# ton-bot.net
KiCad netlist of a schematic drawn in EAGLE
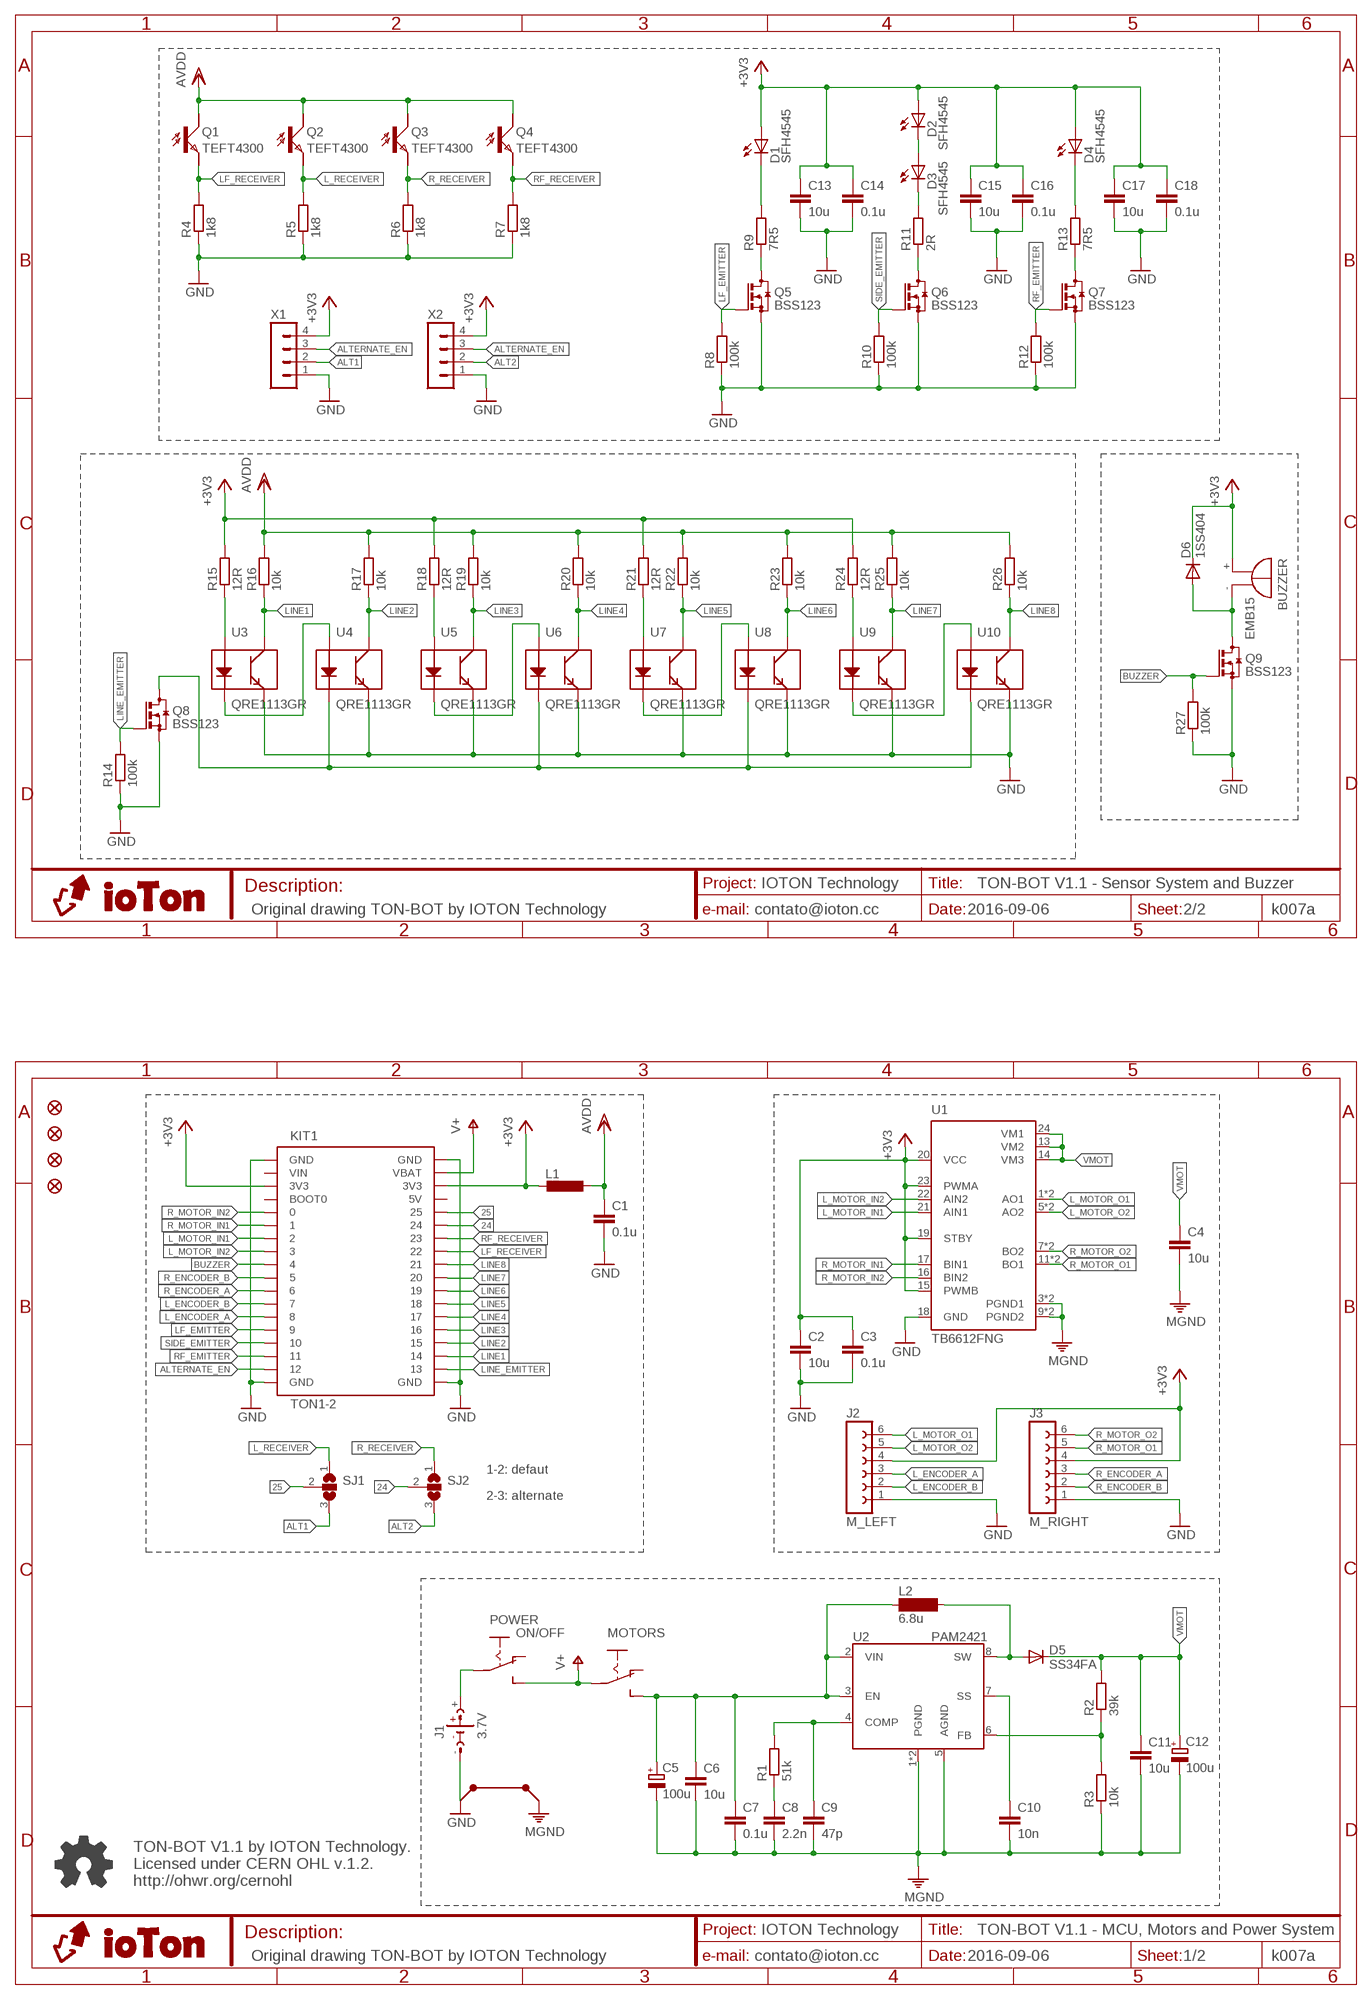
[diagram p0: schematic, sheet 1]

(export (version "E")
  (design (tool "Eeschema 10.0.6"))
  (components
    (comp (ref "BUZZER")
      (value "EMB15")
      (footprint "eagle-import:BMT1205XH7.5")
      (libsource (lib "eagle-import") (part "BMT1205XH7.5"))
    )
    (comp (ref "C1")
      (value "0.1u")
      (footprint "eagle-import:C0603")
      (libsource (lib "eagle-import") (part "C-EUC0603"))
    )
    (comp (ref "C2")
      (value "10u")
      (footprint "eagle-import:C0805")
      (libsource (lib "eagle-import") (part "C-EUC0805"))
    )
    (comp (ref "C3")
      (value "0.1u")
      (footprint "eagle-import:C0603")
      (libsource (lib "eagle-import") (part "C-EUC0603"))
    )
    (comp (ref "C4")
      (value "10u")
      (footprint "eagle-import:C0805")
      (libsource (lib "eagle-import") (part "C-EUC0805"))
    )
    (comp (ref "C5")
      (value "100u")
      (footprint "eagle-import:153CLV-0505")
      (libsource (lib "eagle-import") (part "CPOL-EU153CLV-0505"))
    )
    (comp (ref "C6")
      (value "10u")
      (footprint "eagle-import:C0805")
      (libsource (lib "eagle-import") (part "C-EUC0805"))
    )
    (comp (ref "C7")
      (value "0.1u")
      (footprint "eagle-import:C0603")
      (libsource (lib "eagle-import") (part "C-EUC0603"))
    )
    (comp (ref "C8")
      (value "2.2n")
      (footprint "eagle-import:C0603")
      (libsource (lib "eagle-import") (part "C-EUC0603"))
    )
    (comp (ref "C9")
      (value "47p")
      (footprint "eagle-import:C0603")
      (libsource (lib "eagle-import") (part "C-EUC0603"))
    )
    (comp (ref "C10")
      (value "10n")
      (footprint "eagle-import:C0603")
      (libsource (lib "eagle-import") (part "C-EUC0603"))
    )
    (comp (ref "C11")
      (value "10u")
      (footprint "eagle-import:C0805")
      (libsource (lib "eagle-import") (part "C-EUC0805"))
    )
    (comp (ref "C12")
      (value "100u")
      (footprint "eagle-import:153CLV-0505")
      (libsource (lib "eagle-import") (part "CPOL-EU153CLV-0505"))
    )
    (comp (ref "C13")
      (value "10u")
      (footprint "eagle-import:C0805")
      (libsource (lib "eagle-import") (part "C-EUC0805"))
    )
    (comp (ref "C14")
      (value "0.1u")
      (footprint "eagle-import:C0603")
      (libsource (lib "eagle-import") (part "C-EUC0603"))
    )
    (comp (ref "C15")
      (value "10u")
      (footprint "eagle-import:C0805")
      (libsource (lib "eagle-import") (part "C-EUC0805"))
    )
    (comp (ref "C16")
      (value "0.1u")
      (footprint "eagle-import:C0603")
      (libsource (lib "eagle-import") (part "C-EUC0603"))
    )
    (comp (ref "C17")
      (value "10u")
      (footprint "eagle-import:C0805")
      (libsource (lib "eagle-import") (part "C-EUC0805"))
    )
    (comp (ref "C18")
      (value "0.1u")
      (footprint "eagle-import:C0603")
      (libsource (lib "eagle-import") (part "C-EUC0603"))
    )
    (comp (ref "D1")
      (value "SFH4545")
      (footprint "eagle-import:SFH4545-AK")
      (libsource (lib "eagle-import") (part "SFH4545AK"))
    )
    (comp (ref "D2")
      (value "SFH4545")
      (footprint "eagle-import:SFH4545-KA")
      (libsource (lib "eagle-import") (part "SFH4545KA"))
    )
    (comp (ref "D3")
      (value "SFH4545")
      (footprint "eagle-import:SFH4545-KA")
      (libsource (lib "eagle-import") (part "SFH4545KA"))
    )
    (comp (ref "D4")
      (value "SFH4545")
      (footprint "eagle-import:SFH4545-KA")
      (libsource (lib "eagle-import") (part "SFH4545KA"))
    )
    (comp (ref "D5")
      (value "SS34FA")
      (footprint "eagle-import:DO214BA")
      (libsource (lib "eagle-import") (part "DIODE-DO214BA"))
    )
    (comp (ref "D6")
      (value "1SS404")
      (footprint "eagle-import:SOD323-R")
      (libsource (lib "eagle-import") (part "DIODE-SOD323-R"))
    )
    (comp (ref "J1")
      (value "3.7V")
      (footprint "eagle-import:BATTERY")
      (libsource (lib "eagle-import") (part "BATTERY"))
    )
    (comp (ref "J2")
      (value "M_LEFT")
      (footprint "eagle-import:CON6-1_2MM")
      (libsource (lib "eagle-import") (part "FE06-12MM"))
    )
    (comp (ref "J3")
      (value "M_RIGHT")
      (footprint "eagle-import:CON6-1_2MM")
      (libsource (lib "eagle-import") (part "FE06-12MM"))
    )
    (comp (ref "JP1")
      (value "FIDUCIAL1X2")
      (footprint "eagle-import:FIDUCIAL-1X2")
      (libsource (lib "eagle-import") (part "FIDUCIAL1X2"))
    )
    (comp (ref "JP2")
      (value "FIDUCIAL1X2")
      (footprint "eagle-import:FIDUCIAL-1X2")
      (libsource (lib "eagle-import") (part "FIDUCIAL1X2"))
    )
    (comp (ref "JP3")
      (value "FIDUCIAL1X2")
      (footprint "eagle-import:FIDUCIAL-1X2")
      (libsource (lib "eagle-import") (part "FIDUCIAL1X2"))
    )
    (comp (ref "JP4")
      (value "FIDUCIAL1X2")
      (footprint "eagle-import:FIDUCIAL-1X2")
      (libsource (lib "eagle-import") (part "FIDUCIAL1X2"))
    )
    (comp (ref "KIT1")
      (value "TON1-2")
      (footprint "eagle-import:TON1-2")
      (libsource (lib "eagle-import") (part "TON1-2"))
    )
    (comp (ref "L1")
      (value "L-EUL0603")
      (footprint "eagle-import:L0603")
      (libsource (lib "eagle-import") (part "L-EUL0603"))
    )
    (comp (ref "L2")
      (value "6.8u")
      (footprint "eagle-import:TYS6045")
      (libsource (lib "eagle-import") (part "TYS6045"))
    )
    (comp (ref "MOTORS")
      (value "SWITCHS")
      (footprint "eagle-import:SWITCH")
      (libsource (lib "eagle-import") (part "SWITCHS"))
    )
    (comp (ref "POWER")
      (value "ON/OFF")
      (footprint "eagle-import:SWITCH")
      (libsource (lib "eagle-import") (part "SWITCHS"))
    )
    (comp (ref "Q1")
      (value "TEFT4300")
      (footprint "eagle-import:TEFT4300-CE")
      (libsource (lib "eagle-import") (part "TEFT4300CE"))
    )
    (comp (ref "Q2")
      (value "TEFT4300")
      (footprint "eagle-import:TEFT4300-EC")
      (libsource (lib "eagle-import") (part "TEFT4300EC"))
    )
    (comp (ref "Q3")
      (value "TEFT4300")
      (footprint "eagle-import:TEFT4300-CE")
      (libsource (lib "eagle-import") (part "TEFT4300CE"))
    )
    (comp (ref "Q4")
      (value "TEFT4300")
      (footprint "eagle-import:TEFT4300-EC")
      (libsource (lib "eagle-import") (part "TEFT4300EC"))
    )
    (comp (ref "Q5")
      (value "BSS123")
      (footprint "eagle-import:SOT23")
      (libsource (lib "eagle-import") (part "BSS123"))
    )
    (comp (ref "Q6")
      (value "BSS123")
      (footprint "eagle-import:SOT23")
      (libsource (lib "eagle-import") (part "BSS123"))
    )
    (comp (ref "Q7")
      (value "BSS123")
      (footprint "eagle-import:SOT23")
      (libsource (lib "eagle-import") (part "BSS123"))
    )
    (comp (ref "Q8")
      (value "BSS123")
      (footprint "eagle-import:SOT23")
      (libsource (lib "eagle-import") (part "BSS123"))
    )
    (comp (ref "Q9")
      (value "BSS123")
      (footprint "eagle-import:SOT23")
      (libsource (lib "eagle-import") (part "BSS123"))
    )
    (comp (ref "R1")
      (value "51k")
      (footprint "eagle-import:R0603")
      (libsource (lib "eagle-import") (part "R-EU_R0603"))
    )
    (comp (ref "R2")
      (value "39k")
      (footprint "eagle-import:R0603")
      (libsource (lib "eagle-import") (part "R-EU_R0603"))
    )
    (comp (ref "R3")
      (value "10k")
      (footprint "eagle-import:R0603")
      (libsource (lib "eagle-import") (part "R-EU_R0603"))
    )
    (comp (ref "R4")
      (value "1k8")
      (footprint "eagle-import:R0603")
      (libsource (lib "eagle-import") (part "R-EU_R0603"))
    )
    (comp (ref "R5")
      (value "1k8")
      (footprint "eagle-import:R0603")
      (libsource (lib "eagle-import") (part "R-EU_R0603"))
    )
    (comp (ref "R6")
      (value "1k8")
      (footprint "eagle-import:R0603")
      (libsource (lib "eagle-import") (part "R-EU_R0603"))
    )
    (comp (ref "R7")
      (value "1k8")
      (footprint "eagle-import:R0603")
      (libsource (lib "eagle-import") (part "R-EU_R0603"))
    )
    (comp (ref "R8")
      (value "100k")
      (footprint "eagle-import:R0603")
      (libsource (lib "eagle-import") (part "R-EU_R0603"))
    )
    (comp (ref "R9")
      (value "7R5")
      (footprint "eagle-import:R0805")
      (libsource (lib "eagle-import") (part "R-EU_R0805"))
    )
    (comp (ref "R10")
      (value "100k")
      (footprint "eagle-import:R0603")
      (libsource (lib "eagle-import") (part "R-EU_R0603"))
    )
    (comp (ref "R11")
      (value "2R")
      (footprint "eagle-import:R0805")
      (libsource (lib "eagle-import") (part "R-EU_R0805"))
    )
    (comp (ref "R12")
      (value "100k")
      (footprint "eagle-import:R0603")
      (libsource (lib "eagle-import") (part "R-EU_R0603"))
    )
    (comp (ref "R13")
      (value "7R5")
      (footprint "eagle-import:R0805")
      (libsource (lib "eagle-import") (part "R-EU_R0805"))
    )
    (comp (ref "R14")
      (value "100k")
      (footprint "eagle-import:R0603")
      (libsource (lib "eagle-import") (part "R-EU_R0603"))
    )
    (comp (ref "R15")
      (value "12R")
      (footprint "eagle-import:R0603")
      (libsource (lib "eagle-import") (part "R-EU_R0603"))
    )
    (comp (ref "R16")
      (value "10k")
      (footprint "eagle-import:R0603")
      (libsource (lib "eagle-import") (part "R-EU_R0603"))
    )
    (comp (ref "R17")
      (value "10k")
      (footprint "eagle-import:R0603")
      (libsource (lib "eagle-import") (part "R-EU_R0603"))
    )
    (comp (ref "R18")
      (value "12R")
      (footprint "eagle-import:R0603")
      (libsource (lib "eagle-import") (part "R-EU_R0603"))
    )
    (comp (ref "R19")
      (value "10k")
      (footprint "eagle-import:R0603")
      (libsource (lib "eagle-import") (part "R-EU_R0603"))
    )
    (comp (ref "R20")
      (value "10k")
      (footprint "eagle-import:R0603")
      (libsource (lib "eagle-import") (part "R-EU_R0603"))
    )
    (comp (ref "R21")
      (value "12R")
      (footprint "eagle-import:R0603")
      (libsource (lib "eagle-import") (part "R-EU_R0603"))
    )
    (comp (ref "R22")
      (value "10k")
      (footprint "eagle-import:R0603")
      (libsource (lib "eagle-import") (part "R-EU_R0603"))
    )
    (comp (ref "R23")
      (value "10k")
      (footprint "eagle-import:R0603")
      (libsource (lib "eagle-import") (part "R-EU_R0603"))
    )
    (comp (ref "R24")
      (value "12R")
      (footprint "eagle-import:R0603")
      (libsource (lib "eagle-import") (part "R-EU_R0603"))
    )
    (comp (ref "R25")
      (value "10k")
      (footprint "eagle-import:R0603")
      (libsource (lib "eagle-import") (part "R-EU_R0603"))
    )
    (comp (ref "R26")
      (value "10k")
      (footprint "eagle-import:R0603")
      (libsource (lib "eagle-import") (part "R-EU_R0603"))
    )
    (comp (ref "R27")
      (value "100k")
      (footprint "eagle-import:R0603")
      (libsource (lib "eagle-import") (part "R-EU_R0603"))
    )
    (comp (ref "SJ1")
      (value "SJ2W")
      (footprint "eagle-import:SJ_2")
      (libsource (lib "eagle-import") (part "SJ2W"))
    )
    (comp (ref "SJ2")
      (value "SJ2W")
      (footprint "eagle-import:SJ_2")
      (libsource (lib "eagle-import") (part "SJ2W"))
    )
    (comp (ref "U1")
      (value "TB6612FNG")
      (footprint "eagle-import:SSOP24")
      (libsource (lib "eagle-import") (part "TB6612FNG"))
    )
    (comp (ref "U2")
      (value "PAM2421")
      (footprint "eagle-import:SO-08EP")
      (libsource (lib "eagle-import") (part "PAM242X"))
    )
    (comp (ref "U3")
      (value "QRE1113GR")
      (footprint "eagle-import:QRE1113")
      (libsource (lib "eagle-import") (part "QRE1113"))
    )
    (comp (ref "U4")
      (value "QRE1113GR")
      (footprint "eagle-import:QRE1113")
      (libsource (lib "eagle-import") (part "QRE1113"))
    )
    (comp (ref "U5")
      (value "QRE1113GR")
      (footprint "eagle-import:QRE1113")
      (libsource (lib "eagle-import") (part "QRE1113"))
    )
    (comp (ref "U6")
      (value "QRE1113GR")
      (footprint "eagle-import:QRE1113")
      (libsource (lib "eagle-import") (part "QRE1113"))
    )
    (comp (ref "U7")
      (value "QRE1113GR")
      (footprint "eagle-import:QRE1113")
      (libsource (lib "eagle-import") (part "QRE1113"))
    )
    (comp (ref "U8")
      (value "QRE1113GR")
      (footprint "eagle-import:QRE1113")
      (libsource (lib "eagle-import") (part "QRE1113"))
    )
    (comp (ref "U9")
      (value "QRE1113GR")
      (footprint "eagle-import:QRE1113")
      (libsource (lib "eagle-import") (part "QRE1113"))
    )
    (comp (ref "U10")
      (value "QRE1113GR")
      (footprint "eagle-import:QRE1113")
      (libsource (lib "eagle-import") (part "QRE1113"))
    )
    (comp (ref "X1")
      (value "MA04-1")
      (footprint "eagle-import:PIN4-1")
      (libsource (lib "eagle-import") (part "MA04-1"))
    )
    (comp (ref "X2")
      (value "MA04-1")
      (footprint "eagle-import:PIN4-1")
      (libsource (lib "eagle-import") (part "MA04-1"))
    )
  )
  (nets
    (net (code "1") (name "+3V3") (class "Default")
      (node (ref "BUZZER") (pin "+") (pinfunction "+_+") (pintype "passive"))
      (node (ref "C13") (pin "1") (pinfunction "1_1") (pintype "passive"))
      (node (ref "C14") (pin "1") (pinfunction "1_1") (pintype "passive"))
      (node (ref "C15") (pin "1") (pinfunction "1_1") (pintype "passive"))
      (node (ref "C16") (pin "1") (pinfunction "1_1") (pintype "passive"))
      (node (ref "C17") (pin "1") (pinfunction "1_1") (pintype "passive"))
      (node (ref "C18") (pin "1") (pinfunction "1_1") (pintype "passive"))
      (node (ref "C2") (pin "1") (pinfunction "1_1") (pintype "passive"))
      (node (ref "C3") (pin "1") (pinfunction "1_1") (pintype "passive"))
      (node (ref "D1") (pin "A") (pinfunction "A_A") (pintype "passive"))
      (node (ref "D2") (pin "A") (pinfunction "A_A") (pintype "passive"))
      (node (ref "D4") (pin "A") (pinfunction "A_A") (pintype "passive"))
      (node (ref "D6") (pin "C") (pinfunction "C_C") (pintype "passive"))
      (node (ref "J2") (pin "4") (pinfunction "4_4") (pintype "passive"))
      (node (ref "J3") (pin "4") (pinfunction "4_4") (pintype "passive"))
      (node (ref "KIT1") (pin "EXT-1.3") (pinfunction "3V3_EXT-1.3") (pintype "power_in"))
      (node (ref "KIT1") (pin "EXT-2.3") (pinfunction "3V3_EXT-2.3") (pintype "power_in"))
      (node (ref "L1") (pin "2") (pinfunction "2_2") (pintype "passive"))
      (node (ref "R15") (pin "2") (pinfunction "2_2") (pintype "passive"))
      (node (ref "R18") (pin "2") (pinfunction "2_2") (pintype "passive"))
      (node (ref "R21") (pin "2") (pinfunction "2_2") (pintype "passive"))
      (node (ref "R24") (pin "2") (pinfunction "2_2") (pintype "passive"))
      (node (ref "U1") (pin "15") (pinfunction "PWMB_15") (pintype "input"))
      (node (ref "U1") (pin "19") (pinfunction "STBY_19") (pintype "input"))
      (node (ref "U1") (pin "20") (pinfunction "VCC_20") (pintype "power_in"))
      (node (ref "U1") (pin "23") (pinfunction "PWMA_23") (pintype "input"))
      (node (ref "X1") (pin "4") (pinfunction "4_4") (pintype "passive"))
      (node (ref "X2") (pin "4") (pinfunction "4_4") (pintype "passive"))
    )
    (net (code "2") (name "/5V") (class "Default")
      (node (ref "KIT1") (pin "EXT-2.4") (pinfunction "5V_EXT-2.4") (pintype "power_in"))
    )
    (net (code "3") (name "/VIN") (class "Default")
      (node (ref "KIT1") (pin "EXT-1.2") (pinfunction "VIN_EXT-1.2") (pintype "power_in"))
    )
    (net (code "4") (name "24") (class "Default")
      (node (ref "KIT1") (pin "EXT-2.6") (pinfunction "24_EXT-2.6") (pintype "bidirectional"))
      (node (ref "SJ2") (pin "2") (pinfunction "2_2") (pintype "passive"))
    )
    (net (code "5") (name "25") (class "Default")
      (node (ref "KIT1") (pin "EXT-2.5") (pinfunction "25_EXT-2.5") (pintype "bidirectional"))
      (node (ref "SJ1") (pin "2") (pinfunction "2_2") (pintype "passive"))
    )
    (net (code "6") (name "ALT1") (class "Default")
      (node (ref "SJ1") (pin "3") (pinfunction "3_3") (pintype "passive"))
      (node (ref "X1") (pin "2") (pinfunction "2_2") (pintype "passive"))
    )
    (net (code "7") (name "ALT2") (class "Default")
      (node (ref "SJ2") (pin "3") (pinfunction "3_3") (pintype "passive"))
      (node (ref "X2") (pin "2") (pinfunction "2_2") (pintype "passive"))
    )
    (net (code "8") (name "ALTERNATE_EN") (class "Default")
      (node (ref "KIT1") (pin "EXT-1.17") (pinfunction "12_EXT-1.17") (pintype "bidirectional"))
      (node (ref "X1") (pin "3") (pinfunction "3_3") (pintype "passive"))
      (node (ref "X2") (pin "3") (pinfunction "3_3") (pintype "passive"))
    )
    (net (code "9") (name "AVDD") (class "Default")
      (node (ref "C1") (pin "1") (pinfunction "1_1") (pintype "passive"))
      (node (ref "L1") (pin "1") (pinfunction "1_1") (pintype "passive"))
      (node (ref "Q1") (pin "C") (pinfunction "C_C") (pintype "passive"))
      (node (ref "Q2") (pin "C") (pinfunction "C_C") (pintype "passive"))
      (node (ref "Q3") (pin "C") (pinfunction "C_C") (pintype "passive"))
      (node (ref "Q4") (pin "C") (pinfunction "C_C") (pintype "passive"))
      (node (ref "R16") (pin "2") (pinfunction "2_2") (pintype "passive"))
      (node (ref "R17") (pin "2") (pinfunction "2_2") (pintype "passive"))
      (node (ref "R19") (pin "2") (pinfunction "2_2") (pintype "passive"))
      (node (ref "R20") (pin "2") (pinfunction "2_2") (pintype "passive"))
      (node (ref "R22") (pin "2") (pinfunction "2_2") (pintype "passive"))
      (node (ref "R23") (pin "2") (pinfunction "2_2") (pintype "passive"))
      (node (ref "R25") (pin "2") (pinfunction "2_2") (pintype "passive"))
      (node (ref "R26") (pin "2") (pinfunction "2_2") (pintype "passive"))
    )
    (net (code "10") (name "BUZZER") (class "Default")
      (node (ref "KIT1") (pin "EXT-1.9") (pinfunction "4_EXT-1.9") (pintype "bidirectional"))
      (node (ref "Q9") (pin "1") (pinfunction "G_1") (pintype "passive"))
      (node (ref "R27") (pin "2") (pinfunction "2_2") (pintype "passive"))
    )
    (net (code "11") (name "GND") (class "Default")
      (node (ref "C1") (pin "2") (pinfunction "2_2") (pintype "passive"))
      (node (ref "C13") (pin "2") (pinfunction "2_2") (pintype "passive"))
      (node (ref "C14") (pin "2") (pinfunction "2_2") (pintype "passive"))
      (node (ref "C15") (pin "2") (pinfunction "2_2") (pintype "passive"))
      (node (ref "C16") (pin "2") (pinfunction "2_2") (pintype "passive"))
      (node (ref "C17") (pin "2") (pinfunction "2_2") (pintype "passive"))
      (node (ref "C18") (pin "2") (pinfunction "2_2") (pintype "passive"))
      (node (ref "C2") (pin "2") (pinfunction "2_2") (pintype "passive"))
      (node (ref "C3") (pin "2") (pinfunction "2_2") (pintype "passive"))
      (node (ref "J1") (pin "-") (pinfunction "-_-") (pintype "passive"))
      (node (ref "J2") (pin "1") (pinfunction "1_1") (pintype "passive"))
      (node (ref "J3") (pin "1") (pinfunction "1_1") (pintype "passive"))
      (node (ref "KIT1") (pin "EXT-1.1") (pinfunction "GND_EXT-1.1") (pintype "power_in"))
      (node (ref "KIT1") (pin "EXT-1.18") (pinfunction "GND_EXT-1.18") (pintype "power_in"))
      (node (ref "KIT1") (pin "EXT-2.1") (pinfunction "GND_EXT-2.1") (pintype "power_in"))
      (node (ref "KIT1") (pin "EXT-2.18") (pinfunction "GND_EXT-2.18") (pintype "power_in"))
      (node (ref "KIT1") (pin "GND1") (pinfunction "GND_GND1") (pintype "power_in"))
      (node (ref "KIT1") (pin "GND2") (pinfunction "GND_GND2") (pintype "power_in"))
      (node (ref "Q5") (pin "2") (pinfunction "S_2") (pintype "passive"))
      (node (ref "Q6") (pin "2") (pinfunction "S_2") (pintype "passive"))
      (node (ref "Q7") (pin "2") (pinfunction "S_2") (pintype "passive"))
      (node (ref "Q8") (pin "2") (pinfunction "S_2") (pintype "passive"))
      (node (ref "Q9") (pin "2") (pinfunction "S_2") (pintype "passive"))
      (node (ref "R10") (pin "1") (pinfunction "1_1") (pintype "passive"))
      (node (ref "R12") (pin "1") (pinfunction "1_1") (pintype "passive"))
      (node (ref "R14") (pin "1") (pinfunction "1_1") (pintype "passive"))
      (node (ref "R27") (pin "1") (pinfunction "1_1") (pintype "passive"))
      (node (ref "R4") (pin "1") (pinfunction "1_1") (pintype "passive"))
      (node (ref "R5") (pin "1") (pinfunction "1_1") (pintype "passive"))
      (node (ref "R6") (pin "1") (pinfunction "1_1") (pintype "passive"))
      (node (ref "R7") (pin "1") (pinfunction "1_1") (pintype "passive"))
      (node (ref "R8") (pin "1") (pinfunction "1_1") (pintype "passive"))
      (node (ref "U1") (pin "18") (pinfunction "GND_18") (pintype "power_in"))
      (node (ref "U10") (pin "4") (pinfunction "E_4") (pintype "passive"))
      (node (ref "U3") (pin "4") (pinfunction "E_4") (pintype "passive"))
      (node (ref "U4") (pin "4") (pinfunction "E_4") (pintype "passive"))
      (node (ref "U5") (pin "4") (pinfunction "E_4") (pintype "passive"))
      (node (ref "U6") (pin "4") (pinfunction "E_4") (pintype "passive"))
      (node (ref "U7") (pin "4") (pinfunction "E_4") (pintype "passive"))
      (node (ref "U8") (pin "4") (pinfunction "E_4") (pintype "passive"))
      (node (ref "U9") (pin "4") (pinfunction "E_4") (pintype "passive"))
      (node (ref "X1") (pin "1") (pinfunction "1_1") (pintype "passive"))
      (node (ref "X2") (pin "1") (pinfunction "1_1") (pintype "passive"))
    )
    (net (code "12") (name "LF_EMITTER") (class "Default")
      (node (ref "KIT1") (pin "EXT-1.14") (pinfunction "9_EXT-1.14") (pintype "bidirectional"))
      (node (ref "Q5") (pin "1") (pinfunction "G_1") (pintype "passive"))
      (node (ref "R8") (pin "2") (pinfunction "2_2") (pintype "passive"))
    )
    (net (code "13") (name "LF_RECEIVER") (class "Default")
      (node (ref "KIT1") (pin "EXT-2.8") (pinfunction "22_EXT-2.8") (pintype "bidirectional"))
      (node (ref "Q1") (pin "E") (pinfunction "E_E") (pintype "passive"))
      (node (ref "R4") (pin "2") (pinfunction "2_2") (pintype "passive"))
    )
    (net (code "14") (name "LINE1") (class "Default")
      (node (ref "KIT1") (pin "EXT-2.16") (pinfunction "14_EXT-2.16") (pintype "bidirectional"))
      (node (ref "R16") (pin "1") (pinfunction "1_1") (pintype "passive"))
      (node (ref "U3") (pin "3") (pinfunction "C_3") (pintype "passive"))
    )
    (net (code "15") (name "LINE2") (class "Default")
      (node (ref "KIT1") (pin "EXT-2.15") (pinfunction "15_EXT-2.15") (pintype "bidirectional"))
      (node (ref "R17") (pin "1") (pinfunction "1_1") (pintype "passive"))
      (node (ref "U4") (pin "3") (pinfunction "C_3") (pintype "passive"))
    )
    (net (code "16") (name "LINE3") (class "Default")
      (node (ref "KIT1") (pin "EXT-2.14") (pinfunction "16_EXT-2.14") (pintype "bidirectional"))
      (node (ref "R19") (pin "1") (pinfunction "1_1") (pintype "passive"))
      (node (ref "U5") (pin "3") (pinfunction "C_3") (pintype "passive"))
    )
    (net (code "17") (name "LINE4") (class "Default")
      (node (ref "KIT1") (pin "EXT-2.13") (pinfunction "17_EXT-2.13") (pintype "bidirectional"))
      (node (ref "R20") (pin "1") (pinfunction "1_1") (pintype "passive"))
      (node (ref "U6") (pin "3") (pinfunction "C_3") (pintype "passive"))
    )
    (net (code "18") (name "LINE5") (class "Default")
      (node (ref "KIT1") (pin "EXT-2.12") (pinfunction "18_EXT-2.12") (pintype "bidirectional"))
      (node (ref "R22") (pin "1") (pinfunction "1_1") (pintype "passive"))
      (node (ref "U7") (pin "3") (pinfunction "C_3") (pintype "passive"))
    )
    (net (code "19") (name "LINE6") (class "Default")
      (node (ref "KIT1") (pin "EXT-2.11") (pinfunction "19_EXT-2.11") (pintype "bidirectional"))
      (node (ref "R23") (pin "1") (pinfunction "1_1") (pintype "passive"))
      (node (ref "U8") (pin "3") (pinfunction "C_3") (pintype "passive"))
    )
    (net (code "20") (name "LINE7") (class "Default")
      (node (ref "KIT1") (pin "EXT-2.10") (pinfunction "20_EXT-2.10") (pintype "bidirectional"))
      (node (ref "R25") (pin "1") (pinfunction "1_1") (pintype "passive"))
      (node (ref "U9") (pin "3") (pinfunction "C_3") (pintype "passive"))
    )
    (net (code "21") (name "LINE8") (class "Default")
      (node (ref "KIT1") (pin "EXT-2.9") (pinfunction "21_EXT-2.9") (pintype "bidirectional"))
      (node (ref "R26") (pin "1") (pinfunction "1_1") (pintype "passive"))
      (node (ref "U10") (pin "3") (pinfunction "C_3") (pintype "passive"))
    )
    (net (code "22") (name "LINE_EMITTER") (class "Default")
      (node (ref "KIT1") (pin "EXT-2.17") (pinfunction "13_EXT-2.17") (pintype "bidirectional"))
      (node (ref "Q8") (pin "1") (pinfunction "G_1") (pintype "passive"))
      (node (ref "R14") (pin "2") (pinfunction "2_2") (pintype "passive"))
    )
    (net (code "23") (name "L_ENCODER_A") (class "Default")
      (node (ref "J2") (pin "3") (pinfunction "3_3") (pintype "passive"))
      (node (ref "KIT1") (pin "EXT-1.13") (pinfunction "8_EXT-1.13") (pintype "bidirectional"))
    )
    (net (code "24") (name "L_ENCODER_B") (class "Default")
      (node (ref "J2") (pin "2") (pinfunction "2_2") (pintype "passive"))
      (node (ref "KIT1") (pin "EXT-1.12") (pinfunction "7_EXT-1.12") (pintype "bidirectional"))
    )
    (net (code "25") (name "L_MOTOR_IN1") (class "Default")
      (node (ref "KIT1") (pin "EXT-1.7") (pinfunction "2_EXT-1.7") (pintype "bidirectional"))
      (node (ref "U1") (pin "21") (pinfunction "AIN1_21") (pintype "input"))
    )
    (net (code "26") (name "L_MOTOR_IN2") (class "Default")
      (node (ref "KIT1") (pin "EXT-1.8") (pinfunction "3_EXT-1.8") (pintype "bidirectional"))
      (node (ref "U1") (pin "22") (pinfunction "AIN2_22") (pintype "input"))
    )
    (net (code "27") (name "L_MOTOR_O1") (class "Default")
      (node (ref "J2") (pin "6") (pinfunction "6_6") (pintype "passive"))
      (node (ref "U1") (pin "1") (pinfunction "AO1_1") (pintype "output"))
      (node (ref "U1") (pin "2") (pinfunction "AO1_2") (pintype "output"))
    )
    (net (code "28") (name "L_MOTOR_O2") (class "Default")
      (node (ref "J2") (pin "5") (pinfunction "5_5") (pintype "passive"))
      (node (ref "U1") (pin "5") (pinfunction "AO2_5") (pintype "output"))
      (node (ref "U1") (pin "6") (pinfunction "AO2_6") (pintype "output"))
    )
    (net (code "29") (name "L_RECEIVER") (class "Default")
      (node (ref "Q2") (pin "E") (pinfunction "E_E") (pintype "passive"))
      (node (ref "R5") (pin "2") (pinfunction "2_2") (pintype "passive"))
      (node (ref "SJ1") (pin "1") (pinfunction "1_1") (pintype "passive"))
    )
    (net (code "30") (name "MGND") (class "Default")
      (node (ref "C10") (pin "2") (pinfunction "2_2") (pintype "passive"))
      (node (ref "C11") (pin "2") (pinfunction "2_2") (pintype "passive"))
      (node (ref "C12") (pin "-") (pinfunction "-_-") (pintype "passive"))
      (node (ref "C4") (pin "2") (pinfunction "2_2") (pintype "passive"))
      (node (ref "C5") (pin "-") (pinfunction "-_-") (pintype "passive"))
      (node (ref "C6") (pin "2") (pinfunction "2_2") (pintype "passive"))
      (node (ref "C7") (pin "2") (pinfunction "2_2") (pintype "passive"))
      (node (ref "C8") (pin "2") (pinfunction "2_2") (pintype "passive"))
      (node (ref "C9") (pin "2") (pinfunction "2_2") (pintype "passive"))
      (node (ref "R3") (pin "1") (pinfunction "1_1") (pintype "passive"))
      (node (ref "U1") (pin "10") (pinfunction "PGND2_10") (pintype "power_in"))
      (node (ref "U1") (pin "3") (pinfunction "PGND1_3") (pintype "power_in"))
      (node (ref "U1") (pin "4") (pinfunction "PGND1_4") (pintype "power_in"))
      (node (ref "U1") (pin "9") (pinfunction "PGND2_9") (pintype "power_in"))
      (node (ref "U2") (pin "1") (pinfunction "PGND_1") (pintype "power_in"))
      (node (ref "U2") (pin "5") (pinfunction "AGND_5") (pintype "power_in"))
      (node (ref "U2") (pin "EXP") (pinfunction "PGND_EXP") (pintype "power_in"))
    )
    (net (code "31") (name "Net-(C8-Pad1)") (class "Default")
      (node (ref "C8") (pin "1") (pinfunction "1_1") (pintype "passive"))
      (node (ref "R1") (pin "1") (pinfunction "1_1") (pintype "passive"))
    )
    (net (code "32") (name "Net-(D1-PadK)") (class "Default")
      (node (ref "D1") (pin "K") (pinfunction "K_K") (pintype "passive"))
      (node (ref "R9") (pin "2") (pinfunction "2_2") (pintype "passive"))
    )
    (net (code "33") (name "Net-(D2-PadK)") (class "Default")
      (node (ref "D2") (pin "K") (pinfunction "K_K") (pintype "passive"))
      (node (ref "D3") (pin "A") (pinfunction "A_A") (pintype "passive"))
    )
    (net (code "34") (name "Net-(D3-PadK)") (class "Default")
      (node (ref "D3") (pin "K") (pinfunction "K_K") (pintype "passive"))
      (node (ref "R11") (pin "2") (pinfunction "2_2") (pintype "passive"))
    )
    (net (code "35") (name "Net-(D4-PadK)") (class "Default")
      (node (ref "D4") (pin "K") (pinfunction "K_K") (pintype "passive"))
      (node (ref "R13") (pin "2") (pinfunction "2_2") (pintype "passive"))
    )
    (net (code "36") (name "Net-(J1-Pad+)") (class "Default")
      (node (ref "J1") (pin "+") (pinfunction "+_+") (pintype "passive"))
      (node (ref "POWER") (pin "P") (pinfunction "P_P") (pintype "passive"))
    )
    (net (code "37") (name "Net-(Q5-D)") (class "Default")
      (node (ref "Q5") (pin "3") (pinfunction "D_3") (pintype "passive"))
      (node (ref "R9") (pin "1") (pinfunction "1_1") (pintype "passive"))
    )
    (net (code "38") (name "Net-(Q6-D)") (class "Default")
      (node (ref "Q6") (pin "3") (pinfunction "D_3") (pintype "passive"))
      (node (ref "R11") (pin "1") (pinfunction "1_1") (pintype "passive"))
    )
    (net (code "39") (name "Net-(Q7-D)") (class "Default")
      (node (ref "Q7") (pin "3") (pinfunction "D_3") (pintype "passive"))
      (node (ref "R13") (pin "1") (pinfunction "1_1") (pintype "passive"))
    )
    (net (code "40") (name "Net-(Q8-D)") (class "Default")
      (node (ref "Q8") (pin "3") (pinfunction "D_3") (pintype "passive"))
      (node (ref "U10") (pin "2") (pinfunction "K_2") (pintype "passive"))
      (node (ref "U4") (pin "2") (pinfunction "K_2") (pintype "passive"))
      (node (ref "U6") (pin "2") (pinfunction "K_2") (pintype "passive"))
      (node (ref "U8") (pin "2") (pinfunction "K_2") (pintype "passive"))
    )
    (net (code "41") (name "Net-(Q9-D)") (class "Default")
      (node (ref "BUZZER") (pin "-") (pinfunction "-_-") (pintype "passive"))
      (node (ref "D6") (pin "A") (pinfunction "A_A") (pintype "passive"))
      (node (ref "Q9") (pin "3") (pinfunction "D_3") (pintype "passive"))
    )
    (net (code "42") (name "Net-(U2-COMP)") (class "Default")
      (node (ref "C9") (pin "1") (pinfunction "1_1") (pintype "passive"))
      (node (ref "R1") (pin "2") (pinfunction "2_2") (pintype "passive"))
      (node (ref "U2") (pin "4") (pinfunction "COMP_4") (pintype "passive"))
    )
    (net (code "43") (name "Net-(U2-EN)") (class "Default")
      (node (ref "C5") (pin "+") (pinfunction "+_+") (pintype "passive"))
      (node (ref "C6") (pin "1") (pinfunction "1_1") (pintype "passive"))
      (node (ref "C7") (pin "1") (pinfunction "1_1") (pintype "passive"))
      (node (ref "L2") (pin "1") (pinfunction "1_1") (pintype "passive"))
      (node (ref "MOTORS") (pin "S") (pinfunction "S_S") (pintype "passive"))
      (node (ref "U2") (pin "2") (pinfunction "VIN_2") (pintype "power_in"))
      (node (ref "U2") (pin "3") (pinfunction "EN_3") (pintype "input"))
    )
    (net (code "44") (name "Net-(U2-FB)") (class "Default")
      (node (ref "R2") (pin "1") (pinfunction "1_1") (pintype "passive"))
      (node (ref "R3") (pin "2") (pinfunction "2_2") (pintype "passive"))
      (node (ref "U2") (pin "6") (pinfunction "FB_6") (pintype "input"))
    )
    (net (code "45") (name "Net-(U2-SS)") (class "Default")
      (node (ref "C10") (pin "1") (pinfunction "1_1") (pintype "passive"))
      (node (ref "U2") (pin "7") (pinfunction "SS_7") (pintype "input"))
    )
    (net (code "46") (name "Net-(U2-SW)") (class "Default")
      (node (ref "D5") (pin "A") (pinfunction "A_A") (pintype "passive"))
      (node (ref "L2") (pin "2") (pinfunction "2_2") (pintype "passive"))
      (node (ref "U2") (pin "8") (pinfunction "SW_8") (pintype "output"))
    )
    (net (code "47") (name "Net-(U3-A)") (class "Default")
      (node (ref "R15") (pin "1") (pinfunction "1_1") (pintype "passive"))
      (node (ref "U3") (pin "1") (pinfunction "A_1") (pintype "passive"))
    )
    (net (code "48") (name "Net-(U3-K)") (class "Default")
      (node (ref "U3") (pin "2") (pinfunction "K_2") (pintype "passive"))
      (node (ref "U4") (pin "1") (pinfunction "A_1") (pintype "passive"))
    )
    (net (code "49") (name "Net-(U5-A)") (class "Default")
      (node (ref "R18") (pin "1") (pinfunction "1_1") (pintype "passive"))
      (node (ref "U5") (pin "1") (pinfunction "A_1") (pintype "passive"))
    )
    (net (code "50") (name "Net-(U5-K)") (class "Default")
      (node (ref "U5") (pin "2") (pinfunction "K_2") (pintype "passive"))
      (node (ref "U6") (pin "1") (pinfunction "A_1") (pintype "passive"))
    )
    (net (code "51") (name "Net-(U7-A)") (class "Default")
      (node (ref "R21") (pin "1") (pinfunction "1_1") (pintype "passive"))
      (node (ref "U7") (pin "1") (pinfunction "A_1") (pintype "passive"))
    )
    (net (code "52") (name "Net-(U7-K)") (class "Default")
      (node (ref "U7") (pin "2") (pinfunction "K_2") (pintype "passive"))
      (node (ref "U8") (pin "1") (pinfunction "A_1") (pintype "passive"))
    )
    (net (code "53") (name "Net-(U9-A)") (class "Default")
      (node (ref "R24") (pin "1") (pinfunction "1_1") (pintype "passive"))
      (node (ref "U9") (pin "1") (pinfunction "A_1") (pintype "passive"))
    )
    (net (code "54") (name "Net-(U10-A)") (class "Default")
      (node (ref "U10") (pin "1") (pinfunction "A_1") (pintype "passive"))
      (node (ref "U9") (pin "2") (pinfunction "K_2") (pintype "passive"))
    )
    (net (code "55") (name "RF_EMITTER") (class "Default")
      (node (ref "KIT1") (pin "EXT-1.16") (pinfunction "11_EXT-1.16") (pintype "bidirectional"))
      (node (ref "Q7") (pin "1") (pinfunction "G_1") (pintype "passive"))
      (node (ref "R12") (pin "2") (pinfunction "2_2") (pintype "passive"))
    )
    (net (code "56") (name "RF_RECEIVER") (class "Default")
      (node (ref "KIT1") (pin "EXT-2.7") (pinfunction "23_EXT-2.7") (pintype "bidirectional"))
      (node (ref "Q4") (pin "E") (pinfunction "E_E") (pintype "passive"))
      (node (ref "R7") (pin "2") (pinfunction "2_2") (pintype "passive"))
    )
    (net (code "57") (name "R_ENCODER_A") (class "Default")
      (node (ref "J3") (pin "3") (pinfunction "3_3") (pintype "passive"))
      (node (ref "KIT1") (pin "EXT-1.11") (pinfunction "6_EXT-1.11") (pintype "bidirectional"))
    )
    (net (code "58") (name "R_ENCODER_B") (class "Default")
      (node (ref "J3") (pin "2") (pinfunction "2_2") (pintype "passive"))
      (node (ref "KIT1") (pin "EXT-1.10") (pinfunction "5_EXT-1.10") (pintype "bidirectional"))
    )
    (net (code "59") (name "R_MOTOR_IN1") (class "Default")
      (node (ref "KIT1") (pin "EXT-1.6") (pinfunction "1_EXT-1.6") (pintype "bidirectional"))
      (node (ref "U1") (pin "17") (pinfunction "BIN1_17") (pintype "input"))
    )
    (net (code "60") (name "R_MOTOR_IN2") (class "Default")
      (node (ref "KIT1") (pin "EXT-1.5") (pinfunction "0_EXT-1.5") (pintype "bidirectional"))
      (node (ref "U1") (pin "16") (pinfunction "BIN2_16") (pintype "input"))
    )
    (net (code "61") (name "R_MOTOR_O1") (class "Default")
      (node (ref "J3") (pin "5") (pinfunction "5_5") (pintype "passive"))
      (node (ref "U1") (pin "11") (pinfunction "BO1_11") (pintype "output"))
      (node (ref "U1") (pin "12") (pinfunction "BO1_12") (pintype "output"))
    )
    (net (code "62") (name "R_MOTOR_O2") (class "Default")
      (node (ref "J3") (pin "6") (pinfunction "6_6") (pintype "passive"))
      (node (ref "U1") (pin "7") (pinfunction "BO2_7") (pintype "output"))
      (node (ref "U1") (pin "8") (pinfunction "BO2_8") (pintype "output"))
    )
    (net (code "63") (name "R_RECEIVER") (class "Default")
      (node (ref "Q3") (pin "E") (pinfunction "E_E") (pintype "passive"))
      (node (ref "R6") (pin "2") (pinfunction "2_2") (pintype "passive"))
      (node (ref "SJ2") (pin "1") (pinfunction "1_1") (pintype "passive"))
    )
    (net (code "64") (name "SIDE_EMITTER") (class "Default")
      (node (ref "KIT1") (pin "EXT-1.15") (pinfunction "10_EXT-1.15") (pintype "bidirectional"))
      (node (ref "Q6") (pin "1") (pinfunction "G_1") (pintype "passive"))
      (node (ref "R10") (pin "2") (pinfunction "2_2") (pintype "passive"))
    )
    (net (code "65") (name "V+") (class "Default")
      (node (ref "KIT1") (pin "EXT-2.2") (pinfunction "VBAT_EXT-2.2") (pintype "power_in"))
      (node (ref "MOTORS") (pin "P") (pinfunction "P_P") (pintype "passive"))
      (node (ref "POWER") (pin "S") (pinfunction "S_S") (pintype "passive"))
    )
    (net (code "66") (name "VMOT") (class "Default")
      (node (ref "C11") (pin "1") (pinfunction "1_1") (pintype "passive"))
      (node (ref "C12") (pin "+") (pinfunction "+_+") (pintype "passive"))
      (node (ref "C4") (pin "1") (pinfunction "1_1") (pintype "passive"))
      (node (ref "D5") (pin "C") (pinfunction "C_C") (pintype "passive"))
      (node (ref "R2") (pin "2") (pinfunction "2_2") (pintype "passive"))
      (node (ref "U1") (pin "13") (pinfunction "VM2_13") (pintype "power_in"))
      (node (ref "U1") (pin "14") (pinfunction "VM3_14") (pintype "power_in"))
      (node (ref "U1") (pin "24") (pinfunction "VM1_24") (pintype "power_in"))
    )
    (net (code "67") (name "unconnected-(KIT1-BOOT0-PadEXT-1.4)") (class "Default")
      (node (ref "KIT1") (pin "EXT-1.4") (pinfunction "BOOT0_EXT-1.4") (pintype "input"))
    )
    (net (code "68") (name "unconnected-(MOTORS-PadO)") (class "Default")
      (node (ref "MOTORS") (pin "O") (pinfunction "O_O") (pintype "passive"))
    )
    (net (code "69") (name "unconnected-(POWER-PadO)") (class "Default")
      (node (ref "POWER") (pin "O") (pinfunction "O_O") (pintype "passive"))
    )
  )
)
